# solar_liion.net
KiCad netlist of a schematic drawn in EAGLE
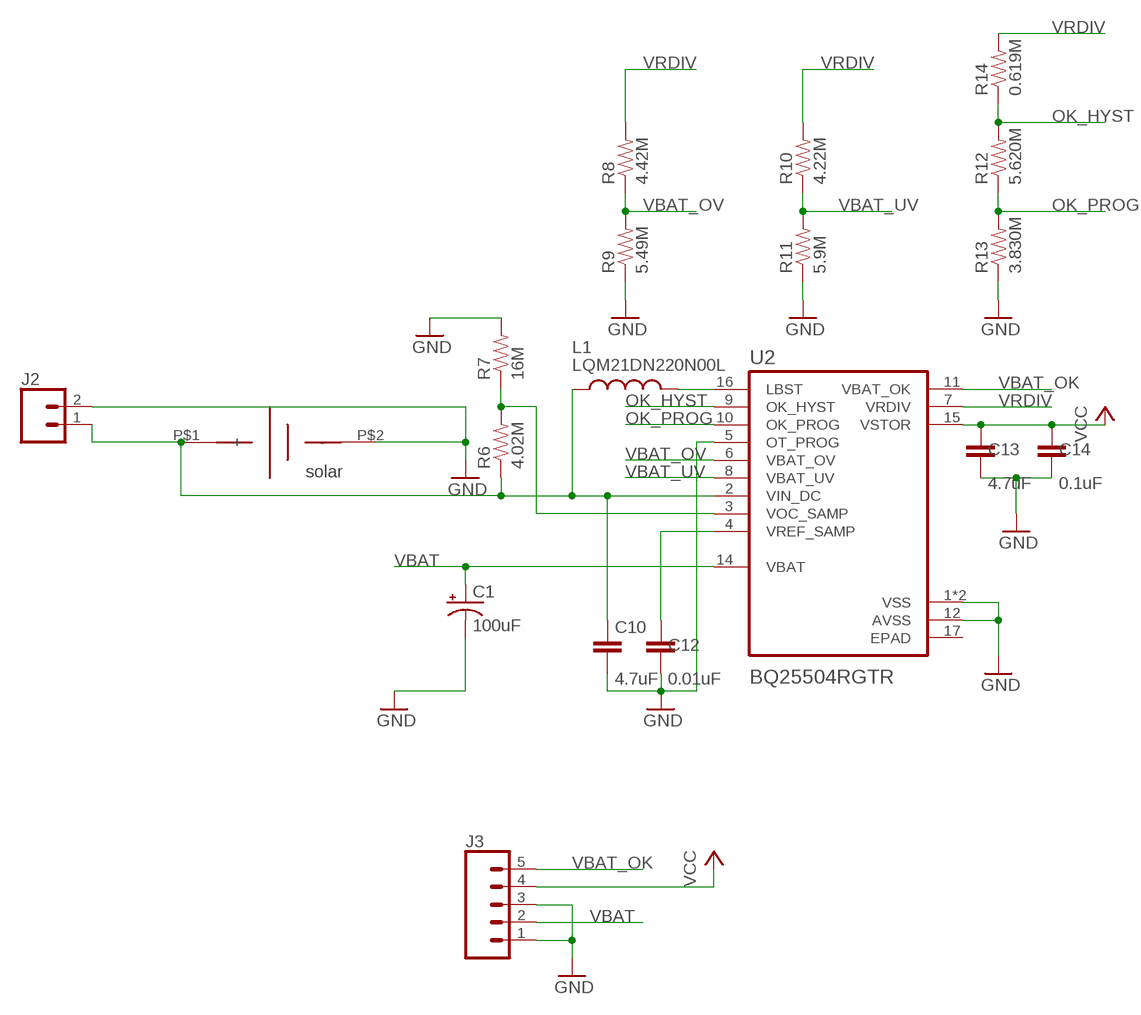
[diagram p0: schematic, sheet 1]

(export (version "E")
  (design (tool "Eeschema 10.0.6"))
  (components
    (comp (ref "C1")
      (value "100uF")
      (footprint "eagle-import:EIA7343")
      (libsource (lib "eagle-import") (part "100UF-POLAR-EIA7343-10V-10%(TANT)"))
    )
    (comp (ref "C10")
      (value "4.7uF")
      (footprint "eagle-import:0603")
      (libsource (lib "eagle-import") (part "10NF-0603-50V-10%"))
    )
    (comp (ref "C12")
      (value "0.01uF")
      (footprint "eagle-import:0603")
      (libsource (lib "eagle-import") (part "10NF-0603-50V-10%"))
    )
    (comp (ref "C13")
      (value "4.7uF")
      (footprint "eagle-import:0603")
      (libsource (lib "eagle-import") (part "10NF-0603-50V-10%"))
    )
    (comp (ref "C14")
      (value "0.1uF")
      (footprint "eagle-import:0603")
      (libsource (lib "eagle-import") (part "10NF-0603-50V-10%"))
    )
    (comp (ref "J2")
      (value "CONN_02")
      (footprint "eagle-import:1X02")
      (libsource (lib "eagle-import") (part "CONN_02"))
    )
    (comp (ref "J3")
      (value "CONN_05")
      (footprint "eagle-import:1X05")
      (libsource (lib "eagle-import") (part "CONN_05"))
    )
    (comp (ref "L1")
      (value "LQM21DN220N00L")
      (footprint "eagle-import:INDC2012X145N")
      (fields (field (name "MF") "Murata"))
      (libsource (lib "eagle-import") (part "LQM21DN220N00L"))
    )
    (comp (ref "R6")
      (value "4.02M")
      (footprint "eagle-import:0603")
      (libsource (lib "eagle-import") (part "470OHM-0603-1/10W-1%"))
    )
    (comp (ref "R7")
      (value "16M")
      (footprint "eagle-import:0603")
      (libsource (lib "eagle-import") (part "470OHM-0603-1/10W-1%"))
    )
    (comp (ref "R8")
      (value "4.42M")
      (footprint "eagle-import:0603")
      (libsource (lib "eagle-import") (part "470OHM-0603-1/10W-1%"))
    )
    (comp (ref "R9")
      (value "5.49M")
      (footprint "eagle-import:0603")
      (libsource (lib "eagle-import") (part "470OHM-0603-1/10W-1%"))
    )
    (comp (ref "R10")
      (value "4.22M")
      (footprint "eagle-import:0603")
      (libsource (lib "eagle-import") (part "470OHM-0603-1/10W-1%"))
    )
    (comp (ref "R11")
      (value "5.9M")
      (footprint "eagle-import:0603")
      (libsource (lib "eagle-import") (part "470OHM-0603-1/10W-1%"))
    )
    (comp (ref "R12")
      (value "5.620M")
      (footprint "eagle-import:0603")
      (libsource (lib "eagle-import") (part "470OHM-0603-1/10W-1%"))
    )
    (comp (ref "R13")
      (value "3.830M")
      (footprint "eagle-import:0603")
      (libsource (lib "eagle-import") (part "470OHM-0603-1/10W-1%"))
    )
    (comp (ref "R14")
      (value "0.619M")
      (footprint "eagle-import:0603")
      (libsource (lib "eagle-import") (part "470OHM-0603-1/10W-1%"))
    )
    (comp (ref "U$3")
      (value "KXOB25-04X3F-TR")
      (footprint "eagle-import:KXOB25-04X3F-TR")
      (libsource (lib "eagle-import") (part "KXOB25-04X3F-TR"))
    )
    (comp (ref "U2")
      (value "BQ25504RGTR")
      (footprint "eagle-import:QFN50P300X300X100-17N")
      (fields (field (name "MF") "Texas Instruments"))
      (libsource (lib "eagle-import") (part "BQ25504RGTR"))
    )
  )
  (nets
    (net (code "1") (name "/EPAD") (class "Default")
      (node (ref "U2") (pin "17") (pinfunction "EPAD_17") (pintype "power_in"))
    )
    (net (code "2") (name "/OK_HYST") (class "Default")
      (node (ref "R12") (pin "2") (pinfunction "2_2") (pintype "passive"))
      (node (ref "R14") (pin "1") (pinfunction "1_1") (pintype "passive"))
      (node (ref "U2") (pin "9") (pinfunction "OK_HYST_9") (pintype "input"))
    )
    (net (code "3") (name "/OK_PROG") (class "Default")
      (node (ref "R12") (pin "1") (pinfunction "1_1") (pintype "passive"))
      (node (ref "R13") (pin "2") (pinfunction "2_2") (pintype "passive"))
      (node (ref "U2") (pin "10") (pinfunction "OK_PROG_10") (pintype "input"))
    )
    (net (code "4") (name "/VBAT") (class "Default")
      (node (ref "C1") (pin "A") (pinfunction "+_A") (pintype "passive"))
      (node (ref "J3") (pin "2") (pinfunction "2_2") (pintype "passive"))
      (node (ref "U2") (pin "14") (pinfunction "VBAT_14") (pintype "bidirectional"))
    )
    (net (code "5") (name "/VBAT_OK") (class "Default")
      (node (ref "J3") (pin "5") (pinfunction "5_5") (pintype "passive"))
      (node (ref "U2") (pin "11") (pinfunction "VBAT_OK_11") (pintype "output"))
    )
    (net (code "6") (name "/VBAT_OV") (class "Default")
      (node (ref "R8") (pin "1") (pinfunction "1_1") (pintype "passive"))
      (node (ref "R9") (pin "2") (pinfunction "2_2") (pintype "passive"))
      (node (ref "U2") (pin "6") (pinfunction "VBAT_OV_6") (pintype "input"))
    )
    (net (code "7") (name "/VBAT_UV") (class "Default")
      (node (ref "R10") (pin "1") (pinfunction "1_1") (pintype "passive"))
      (node (ref "R11") (pin "2") (pinfunction "2_2") (pintype "passive"))
      (node (ref "U2") (pin "8") (pinfunction "VBAT_UV_8") (pintype "input"))
    )
    (net (code "8") (name "/VRDIV") (class "Default")
      (node (ref "R10") (pin "2") (pinfunction "2_2") (pintype "passive"))
      (node (ref "R14") (pin "2") (pinfunction "2_2") (pintype "passive"))
      (node (ref "R8") (pin "2") (pinfunction "2_2") (pintype "passive"))
      (node (ref "U2") (pin "7") (pinfunction "VRDIV_7") (pintype "output"))
    )
    (net (code "9") (name "GND") (class "Default")
      (node (ref "C1") (pin "C") (pinfunction "-_C") (pintype "passive"))
      (node (ref "C10") (pin "2") (pinfunction "2_2") (pintype "passive"))
      (node (ref "C12") (pin "2") (pinfunction "2_2") (pintype "passive"))
      (node (ref "C13") (pin "2") (pinfunction "2_2") (pintype "passive"))
      (node (ref "C14") (pin "2") (pinfunction "2_2") (pintype "passive"))
      (node (ref "J2") (pin "2") (pinfunction "2_2") (pintype "passive"))
      (node (ref "J3") (pin "1") (pinfunction "1_1") (pintype "passive"))
      (node (ref "J3") (pin "3") (pinfunction "3_3") (pintype "passive"))
      (node (ref "R11") (pin "1") (pinfunction "1_1") (pintype "passive"))
      (node (ref "R13") (pin "1") (pinfunction "1_1") (pintype "passive"))
      (node (ref "R7") (pin "2") (pinfunction "2_2") (pintype "passive"))
      (node (ref "R9") (pin "1") (pinfunction "1_1") (pintype "passive"))
      (node (ref "U$3") (pin "P$2") (pinfunction "-_P$2") (pintype "bidirectional"))
      (node (ref "U2") (pin "1") (pinfunction "VSS_1") (pintype "power_in"))
      (node (ref "U2") (pin "12") (pinfunction "AVSS_12") (pintype "power_in"))
      (node (ref "U2") (pin "13") (pinfunction "VSS_13") (pintype "power_in"))
      (node (ref "U2") (pin "5") (pinfunction "OT_PROG_5") (pintype "input"))
    )
    (net (code "10") (name "Net-(U$3-+)") (class "Default")
      (node (ref "C10") (pin "1") (pinfunction "1_1") (pintype "passive"))
      (node (ref "J2") (pin "1") (pinfunction "1_1") (pintype "passive"))
      (node (ref "L1") (pin "1") (pinfunction "1_1") (pintype "passive"))
      (node (ref "R6") (pin "1") (pinfunction "1_1") (pintype "passive"))
      (node (ref "U$3") (pin "P$1") (pinfunction "+_P$1") (pintype "bidirectional"))
      (node (ref "U2") (pin "2") (pinfunction "VIN_DC_2") (pintype "input"))
    )
    (net (code "11") (name "Net-(U2-LBST)") (class "Default")
      (node (ref "L1") (pin "2") (pinfunction "2_2") (pintype "passive"))
      (node (ref "U2") (pin "16") (pinfunction "LBST_16") (pintype "input"))
    )
    (net (code "12") (name "Net-(U2-VOC_SAMP)") (class "Default")
      (node (ref "R6") (pin "2") (pinfunction "2_2") (pintype "passive"))
      (node (ref "R7") (pin "1") (pinfunction "1_1") (pintype "passive"))
      (node (ref "U2") (pin "3") (pinfunction "VOC_SAMP_3") (pintype "input"))
    )
    (net (code "13") (name "Net-(U2-VREF_SAMP)") (class "Default")
      (node (ref "C12") (pin "1") (pinfunction "1_1") (pintype "passive"))
      (node (ref "U2") (pin "4") (pinfunction "VREF_SAMP_4") (pintype "input"))
    )
    (net (code "14") (name "VCC") (class "Default")
      (node (ref "C13") (pin "1") (pinfunction "1_1") (pintype "passive"))
      (node (ref "C14") (pin "1") (pinfunction "1_1") (pintype "passive"))
      (node (ref "J3") (pin "4") (pinfunction "4_4") (pintype "passive"))
      (node (ref "U2") (pin "15") (pinfunction "VSTOR_15") (pintype "output"))
    )
  )
)
